# tdlf_steamy_streamer_top_modulaire.net
KiCad netlist of a schematic drawn in EAGLE
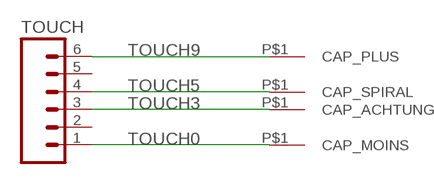
[diagram p0: schematic, sheet 1]

(export (version "E")
  (design (tool "Eeschema 10.0.6"))
  (components
    (comp (ref "CAP_PLUS")
      (value "TDLF_CAP_PLUS")
      (footprint "eagle-import:TDLF_CAP_PLUS")
      (libsource (lib "eagle-import") (part "TDLF_CAP_PLUS"))
    )
    (comp (ref "TOUCH")
      (value "M06SMD-STRAIGHT-COMBO-FEMALE")
      (footprint "eagle-import:1X06_SMD_STRAIGHT_COMBO")
      (libsource (lib "eagle-import") (part "M06SMD-STRAIGHT-COMBO-FEMALE"))
    )
    (comp (ref "U$1")
      (value "TDLF_CAP_MOINS")
      (footprint "eagle-import:TDLF_CAP_MOINS")
      (libsource (lib "eagle-import") (part "TDLF_CAP_MOINS"))
    )
    (comp (ref "U$2")
      (value "TDLF_CAP_SPIRAL")
      (footprint "eagle-import:TDLF_CAP_SPIRAL")
      (libsource (lib "eagle-import") (part "TDLF_CAP_SPIRAL"))
    )
    (comp (ref "U$4")
      (value "TDLF_CAP_ACHTUNG")
      (footprint "eagle-import:TDLF_CAP_ACHTUNG")
      (libsource (lib "eagle-import") (part "TDLF_CAP_ACHTUNG"))
    )
  )
  (nets
    (net (code "1") (name "/TOUCH0") (class "Default")
      (node (ref "TOUCH") (pin "1") (pinfunction "1_1") (pintype "passive"))
      (node (ref "U$1") (pin "P$1") (pinfunction "CAP_MOINS_P$1") (pintype "bidirectional"))
    )
    (net (code "2") (name "/TOUCH3") (class "Default")
      (node (ref "TOUCH") (pin "3") (pinfunction "3_3") (pintype "passive"))
      (node (ref "U$4") (pin "P$1") (pinfunction "CAP_ACHTUNG_P$1") (pintype "bidirectional"))
    )
    (net (code "3") (name "/TOUCH5") (class "Default")
      (node (ref "TOUCH") (pin "4") (pinfunction "4_4") (pintype "passive"))
      (node (ref "U$2") (pin "P$1") (pinfunction "CAP_SPIRAL_P$1") (pintype "bidirectional"))
    )
    (net (code "4") (name "/TOUCH9") (class "Default")
      (node (ref "CAP_PLUS") (pin "P$1") (pinfunction "CAP_PLUS_P$1") (pintype "bidirectional"))
      (node (ref "TOUCH") (pin "6") (pinfunction "6_6") (pintype "passive"))
    )
    (net (code "5") (name "unconnected-(TOUCH-Pad2)") (class "Default")
      (node (ref "TOUCH") (pin "2") (pinfunction "2_2") (pintype "passive"))
    )
    (net (code "6") (name "unconnected-(TOUCH-Pad5)") (class "Default")
      (node (ref "TOUCH") (pin "5") (pinfunction "5_5") (pintype "passive"))
    )
  )
)
